# main_bottom.net
KiCad netlist of a schematic drawn in EAGLE
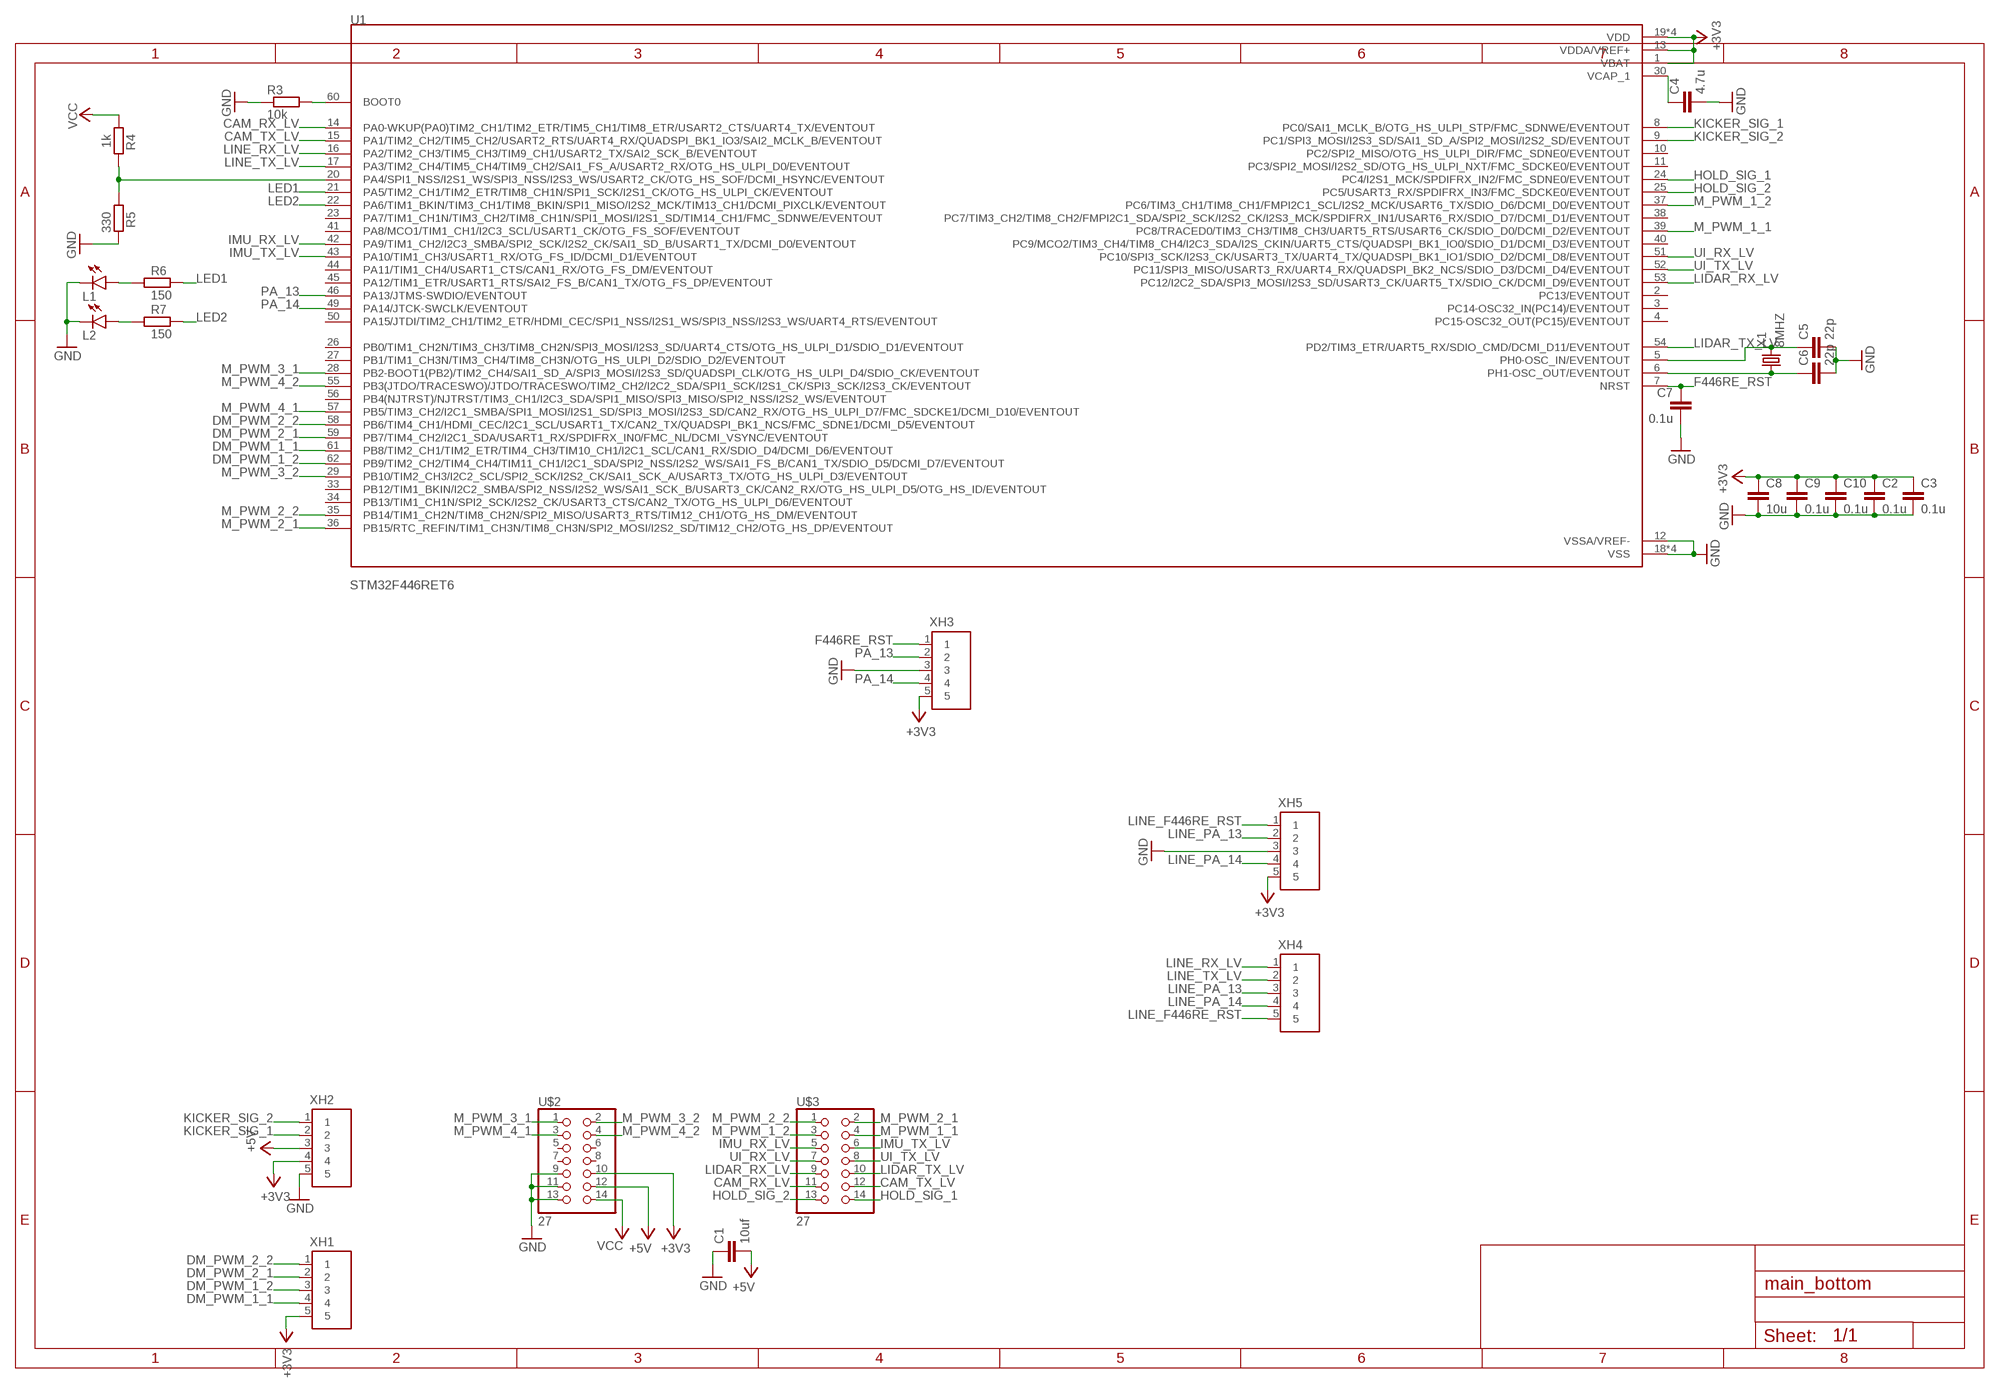
[diagram p0: schematic, sheet 1]

(export (version "E")
  (design (tool "Eeschema 10.0.6"))
  (components
    (comp (ref "C1")
      (value "10uf")
      (footprint "eagle-import:C0805")
      (libsource (lib "eagle-import") (part "C-EUC0805"))
    )
    (comp (ref "C2")
      (value "0.1u")
      (footprint "eagle-import:C0603")
      (libsource (lib "eagle-import") (part "C-EUC0603"))
    )
    (comp (ref "C3")
      (value "0.1u")
      (footprint "eagle-import:C0603")
      (libsource (lib "eagle-import") (part "C-EUC0603"))
    )
    (comp (ref "C4")
      (value "4.7u")
      (footprint "eagle-import:C0603")
      (libsource (lib "eagle-import") (part "C-EUC0603"))
    )
    (comp (ref "C5")
      (value "22p")
      (footprint "eagle-import:C0603")
      (libsource (lib "eagle-import") (part "C-EUC0603"))
    )
    (comp (ref "C6")
      (value "22p")
      (footprint "eagle-import:C0603")
      (libsource (lib "eagle-import") (part "C-EUC0603"))
    )
    (comp (ref "C7")
      (value "0.1u")
      (footprint "eagle-import:C0603")
      (libsource (lib "eagle-import") (part "C-EUC0603"))
    )
    (comp (ref "C8")
      (value "10u")
      (footprint "eagle-import:C0805")
      (libsource (lib "eagle-import") (part "C-EUC0805"))
    )
    (comp (ref "C9")
      (value "0.1u")
      (footprint "eagle-import:C0603")
      (libsource (lib "eagle-import") (part "C-EUC0603"))
    )
    (comp (ref "C10")
      (value "0.1u")
      (footprint "eagle-import:C0603")
      (libsource (lib "eagle-import") (part "C-EUC0603"))
    )
    (comp (ref "L1")
      (value "SML-E12P8WT86")
      (footprint "eagle-import:LED_SML-LXFM0603SIC-TR")
      (libsource (lib "eagle-import") (part "SML-E12P8WT86"))
    )
    (comp (ref "L2")
      (value "SML-E12P8WT86")
      (footprint "eagle-import:LED_SML-LXFM0603SIC-TR")
      (libsource (lib "eagle-import") (part "SML-E12P8WT86"))
    )
    (comp (ref "R3")
      (value "10k")
      (footprint "eagle-import:R0603")
      (libsource (lib "eagle-import") (part "R-EU_R0603"))
    )
    (comp (ref "R4")
      (value "1k")
      (footprint "eagle-import:R0603")
      (libsource (lib "eagle-import") (part "R-EU_R0603"))
    )
    (comp (ref "R5")
      (value "330")
      (footprint "eagle-import:R0603")
      (libsource (lib "eagle-import") (part "R-EU_R0603"))
    )
    (comp (ref "R6")
      (value "150")
      (footprint "eagle-import:R0603")
      (libsource (lib "eagle-import") (part "R-EU_R0603"))
    )
    (comp (ref "R7")
      (value "150")
      (footprint "eagle-import:R0603")
      (libsource (lib "eagle-import") (part "R-EU_R0603"))
    )
    (comp (ref "U$2")
      (value "27")
      (footprint "eagle-import:2_7")
      (libsource (lib "eagle-import") (part "27"))
    )
    (comp (ref "U$3")
      (value "27")
      (footprint "eagle-import:2_7")
      (libsource (lib "eagle-import") (part "27"))
    )
    (comp (ref "U1")
      (value "STM32F446RET6")
      (footprint "eagle-import:QFP50P1200X1200X160-64N")
      (fields (field (name "MF") "STMicroelectronics"))
      (libsource (lib "eagle-import") (part "STM32F446RET6"))
    )
    (comp (ref "X1")
      (value "8MHZ")
      (footprint "eagle-import:16MHZ")
      (libsource (lib "eagle-import") (part "16MHZ"))
    )
    (comp (ref "XH1")
      (value "S5B")
      (footprint "eagle-import:S5B")
      (libsource (lib "eagle-import") (part "S5B"))
    )
    (comp (ref "XH2")
      (value "S5B")
      (footprint "eagle-import:S5B")
      (libsource (lib "eagle-import") (part "S5B"))
    )
    (comp (ref "XH3")
      (value "S5B")
      (footprint "eagle-import:S5B")
      (libsource (lib "eagle-import") (part "S5B"))
    )
    (comp (ref "XH4")
      (value "S5B")
      (footprint "eagle-import:S5B")
      (libsource (lib "eagle-import") (part "S5B"))
    )
    (comp (ref "XH5")
      (value "S5B")
      (footprint "eagle-import:S5B")
      (libsource (lib "eagle-import") (part "S5B"))
    )
  )
  (nets
    (net (code "1") (name "+3V3") (class "Default")
      (node (ref "C10") (pin "1") (pinfunction "1_1") (pintype "passive"))
      (node (ref "C2") (pin "1") (pinfunction "1_1") (pintype "passive"))
      (node (ref "C3") (pin "1") (pinfunction "1_1") (pintype "passive"))
      (node (ref "C8") (pin "1") (pinfunction "1_1") (pintype "passive"))
      (node (ref "C9") (pin "1") (pinfunction "1_1") (pintype "passive"))
      (node (ref "U$2") (pin "10") (pinfunction "10_10") (pintype "passive"))
      (node (ref "U1") (pin "1") (pinfunction "VBAT_1") (pintype "power_in"))
      (node (ref "U1") (pin "13") (pinfunction "VDDA/VREF+_13") (pintype "power_in"))
      (node (ref "U1") (pin "19") (pinfunction "VDD_19") (pintype "power_in"))
      (node (ref "U1") (pin "32") (pinfunction "VDD_32") (pintype "power_in"))
      (node (ref "U1") (pin "48") (pinfunction "VDD_48") (pintype "power_in"))
      (node (ref "U1") (pin "64") (pinfunction "VDD_64") (pintype "power_in"))
      (node (ref "XH1") (pin "5") (pinfunction "5_5") (pintype "bidirectional"))
      (node (ref "XH2") (pin "4") (pinfunction "4_4") (pintype "bidirectional"))
      (node (ref "XH3") (pin "5") (pinfunction "5_5") (pintype "bidirectional"))
      (node (ref "XH5") (pin "5") (pinfunction "5_5") (pintype "bidirectional"))
    )
    (net (code "2") (name "+5V") (class "Default")
      (node (ref "C1") (pin "2") (pinfunction "2_2") (pintype "passive"))
      (node (ref "U$2") (pin "12") (pinfunction "12_12") (pintype "passive"))
      (node (ref "XH2") (pin "3") (pinfunction "3_3") (pintype "bidirectional"))
    )
    (net (code "3") (name "/CAM_RX_LV") (class "Default")
      (node (ref "U$3") (pin "11") (pinfunction "11_11") (pintype "passive"))
      (node (ref "U1") (pin "14") (pinfunction "PA0-WKUP(PA0)TIM2_CH1/TIM2_ETR/TIM5_CH1/TIM8_ETR/USART2_CTS/UART4_TX/EVENTOUT_14") (pintype "bidirectional"))
    )
    (net (code "4") (name "/CAM_TX_LV") (class "Default")
      (node (ref "U$3") (pin "12") (pinfunction "12_12") (pintype "passive"))
      (node (ref "U1") (pin "15") (pinfunction "PA1/TIM2_CH2/TIM5_CH2/USART2_RTS/UART4_RX/QUADSPI_BK1_IO3/SAI2_MCLK_B/EVENTOUT_15") (pintype "bidirectional"))
    )
    (net (code "5") (name "/DM_PWM_1_1") (class "Default")
      (node (ref "U1") (pin "61") (pinfunction "PB8/TIM2_CH1/TIM2_ETR/TIM4_CH3/TIM10_CH1/I2C1_SCL/CAN1_RX/SDIO_D4/DCMI_D6/EVENTOUT_61") (pintype "bidirectional"))
      (node (ref "XH1") (pin "4") (pinfunction "4_4") (pintype "bidirectional"))
    )
    (net (code "6") (name "/DM_PWM_1_2") (class "Default")
      (node (ref "U1") (pin "62") (pinfunction "PB9/TIM2_CH2/TIM4_CH4/TIM11_CH1/I2C1_SDA/SPI2_NSS/I2S2_WS/SAI1_FS_B/CAN1_TX/SDIO_D5/DCMI_D7/EVENTOUT_62") (pintype "bidirectional"))
      (node (ref "XH1") (pin "3") (pinfunction "3_3") (pintype "bidirectional"))
    )
    (net (code "7") (name "/DM_PWM_2_1") (class "Default")
      (node (ref "U1") (pin "59") (pinfunction "PB7/TIM4_CH2/I2C1_SDA/USART1_RX/SPDIFRX_IN0/FMC_NL/DCMI_VSYNC/EVENTOUT_59") (pintype "bidirectional"))
      (node (ref "XH1") (pin "2") (pinfunction "2_2") (pintype "bidirectional"))
    )
    (net (code "8") (name "/DM_PWM_2_2") (class "Default")
      (node (ref "U1") (pin "58") (pinfunction "PB6/TIM4_CH1/HDMI_CEC/I2C1_SCL/USART1_TX/CAN2_TX/QUADSPI_BK1_NCS/FMC_SDNE1/DCMI_D5/EVENTOUT_58") (pintype "bidirectional"))
      (node (ref "XH1") (pin "1") (pinfunction "1_1") (pintype "bidirectional"))
    )
    (net (code "9") (name "/F446RE_RST") (class "Default")
      (node (ref "C7") (pin "1") (pinfunction "1_1") (pintype "passive"))
      (node (ref "U1") (pin "7") (pinfunction "NRST_7") (pintype "bidirectional"))
      (node (ref "XH3") (pin "1") (pinfunction "1_1") (pintype "bidirectional"))
    )
    (net (code "10") (name "/HOLD_SIG_1") (class "Default")
      (node (ref "U$3") (pin "14") (pinfunction "14_14") (pintype "passive"))
      (node (ref "U1") (pin "24") (pinfunction "PC4/I2S1_MCK/SPDIFRX_IN2/FMC_SDNE0/EVENTOUT_24") (pintype "bidirectional"))
    )
    (net (code "11") (name "/HOLD_SIG_2") (class "Default")
      (node (ref "U$3") (pin "13") (pinfunction "13_13") (pintype "passive"))
      (node (ref "U1") (pin "25") (pinfunction "PC5/USART3_RX/SPDIFRX_IN3/FMC_SDCKE0/EVENTOUT_25") (pintype "bidirectional"))
    )
    (net (code "12") (name "/IMU_RX_LV") (class "Default")
      (node (ref "U$3") (pin "5") (pinfunction "5_5") (pintype "passive"))
      (node (ref "U1") (pin "42") (pinfunction "PA9/TIM1_CH2/I2C3_SMBA/SPI2_SCK/I2S2_CK/SAI1_SD_B/USART1_TX/DCMI_D0/EVENTOUT_42") (pintype "bidirectional"))
    )
    (net (code "13") (name "/IMU_TX_LV") (class "Default")
      (node (ref "U$3") (pin "6") (pinfunction "6_6") (pintype "passive"))
      (node (ref "U1") (pin "43") (pinfunction "PA10/TIM1_CH3/USART1_RX/OTG_FS_ID/DCMI_D1/EVENTOUT_43") (pintype "bidirectional"))
    )
    (net (code "14") (name "/KICKER_SIG_1") (class "Default")
      (node (ref "U1") (pin "8") (pinfunction "PC0/SAI1_MCLK_B/OTG_HS_ULPI_STP/FMC_SDNWE/EVENTOUT_8") (pintype "bidirectional"))
      (node (ref "XH2") (pin "2") (pinfunction "2_2") (pintype "bidirectional"))
    )
    (net (code "15") (name "/KICKER_SIG_2") (class "Default")
      (node (ref "U1") (pin "9") (pinfunction "PC1/SPI3_MOSI/I2S3_SD/SAI1_SD_A/SPI2_MOSI/I2S2_SD/EVENTOUT_9") (pintype "bidirectional"))
      (node (ref "XH2") (pin "1") (pinfunction "1_1") (pintype "bidirectional"))
    )
    (net (code "16") (name "/LED1") (class "Default")
      (node (ref "R6") (pin "2") (pinfunction "2_2") (pintype "passive"))
      (node (ref "U1") (pin "21") (pinfunction "PA5/TIM2_CH1/TIM2_ETR/TIM8_CH1N/SPI1_SCK/I2S1_CK/OTG_HS_ULPI_CK/EVENTOUT_21") (pintype "bidirectional"))
    )
    (net (code "17") (name "/LED2") (class "Default")
      (node (ref "R7") (pin "2") (pinfunction "2_2") (pintype "passive"))
      (node (ref "U1") (pin "22") (pinfunction "PA6/TIM1_BKIN/TIM3_CH1/TIM8_BKIN/SPI1_MISO/I2S2_MCK/TIM13_CH1/DCMI_PIXCLK/EVENTOUT_22") (pintype "bidirectional"))
    )
    (net (code "18") (name "/LIDAR_RX_LV") (class "Default")
      (node (ref "U$3") (pin "9") (pinfunction "9_9") (pintype "passive"))
      (node (ref "U1") (pin "53") (pinfunction "PC12/I2C2_SDA/SPI3_MOSI/I2S3_SD/USART3_CK/UART5_TX/SDIO_CK/DCMI_D9/EVENTOUT_53") (pintype "bidirectional"))
    )
    (net (code "19") (name "/LIDAR_TX_LV") (class "Default")
      (node (ref "U$3") (pin "10") (pinfunction "10_10") (pintype "passive"))
      (node (ref "U1") (pin "54") (pinfunction "PD2/TIM3_ETR/UART5_RX/SDIO_CMD/DCMI_D11/EVENTOUT_54") (pintype "bidirectional"))
    )
    (net (code "20") (name "/LINE_F446RE_RST") (class "Default")
      (node (ref "XH4") (pin "5") (pinfunction "5_5") (pintype "bidirectional"))
      (node (ref "XH5") (pin "1") (pinfunction "1_1") (pintype "bidirectional"))
    )
    (net (code "21") (name "/LINE_PA_13") (class "Default")
      (node (ref "XH4") (pin "3") (pinfunction "3_3") (pintype "bidirectional"))
      (node (ref "XH5") (pin "2") (pinfunction "2_2") (pintype "bidirectional"))
    )
    (net (code "22") (name "/LINE_PA_14") (class "Default")
      (node (ref "XH4") (pin "4") (pinfunction "4_4") (pintype "bidirectional"))
      (node (ref "XH5") (pin "4") (pinfunction "4_4") (pintype "bidirectional"))
    )
    (net (code "23") (name "/LINE_RX_LV") (class "Default")
      (node (ref "U1") (pin "16") (pinfunction "PA2/TIM2_CH3/TIM5_CH3/TIM9_CH1/USART2_TX/SAI2_SCK_B/EVENTOUT_16") (pintype "bidirectional"))
      (node (ref "XH4") (pin "1") (pinfunction "1_1") (pintype "bidirectional"))
    )
    (net (code "24") (name "/LINE_TX_LV") (class "Default")
      (node (ref "U1") (pin "17") (pinfunction "PA3/TIM2_CH4/TIM5_CH4/TIM9_CH2/SAI1_FS_A/USART2_RX/OTG_HS_ULPI_D0/EVENTOUT_17") (pintype "bidirectional"))
      (node (ref "XH4") (pin "2") (pinfunction "2_2") (pintype "bidirectional"))
    )
    (net (code "25") (name "/M_PWM_1_1") (class "Default")
      (node (ref "U$3") (pin "4") (pinfunction "4_4") (pintype "passive"))
      (node (ref "U1") (pin "39") (pinfunction "PC8/TRACED0/TIM3_CH3/TIM8_CH3/UART5_RTS/USART6_CK/SDIO_D0/DCMI_D2/EVENTOUT_39") (pintype "bidirectional"))
    )
    (net (code "26") (name "/M_PWM_1_2") (class "Default")
      (node (ref "U$3") (pin "3") (pinfunction "3_3") (pintype "passive"))
      (node (ref "U1") (pin "37") (pinfunction "PC6/TIM3_CH1/TIM8_CH1/FMPI2C1_SCL/I2S2_MCK/USART6_TX/SDIO_D6/DCMI_D0/EVENTOUT_37") (pintype "bidirectional"))
    )
    (net (code "27") (name "/M_PWM_2_1") (class "Default")
      (node (ref "U$3") (pin "2") (pinfunction "2_2") (pintype "passive"))
      (node (ref "U1") (pin "36") (pinfunction "PB15/RTC_REFIN/TIM1_CH3N/TIM8_CH3N/SPI2_MOSI/I2S2_SD/TIM12_CH2/OTG_HS_DP/EVENTOUT_36") (pintype "bidirectional"))
    )
    (net (code "28") (name "/M_PWM_2_2") (class "Default")
      (node (ref "U$3") (pin "1") (pinfunction "1_1") (pintype "passive"))
      (node (ref "U1") (pin "35") (pinfunction "PB14/TIM1_CH2N/TIM8_CH2N/SPI2_MISO/USART3_RTS/TIM12_CH1/OTG_HS_DM/EVENTOUT_35") (pintype "bidirectional"))
    )
    (net (code "29") (name "/M_PWM_3_1") (class "Default")
      (node (ref "U$2") (pin "1") (pinfunction "1_1") (pintype "passive"))
      (node (ref "U1") (pin "28") (pinfunction "PB2-BOOT1(PB2)/TIM2_CH4/SAI1_SD_A/SPI3_MOSI/I2S3_SD/QUADSPI_CLK/OTG_HS_ULPI_D4/SDIO_CK/EVENTOUT_28") (pintype "bidirectional"))
    )
    (net (code "30") (name "/M_PWM_3_2") (class "Default")
      (node (ref "U$2") (pin "2") (pinfunction "2_2") (pintype "passive"))
      (node (ref "U1") (pin "29") (pinfunction "PB10/TIM2_CH3/I2C2_SCL/SPI2_SCK/I2S2_CK/SAI1_SCK_A/USART3_TX/OTG_HS_ULPI_D3/EVENTOUT_29") (pintype "bidirectional"))
    )
    (net (code "31") (name "/M_PWM_4_1") (class "Default")
      (node (ref "U$2") (pin "3") (pinfunction "3_3") (pintype "passive"))
      (node (ref "U1") (pin "57") (pinfunction "PB5/TIM3_CH2/I2C1_SMBA/SPI1_MOSI/I2S1_SD/SPI3_MOSI/I2S3_SD/CAN2_RX/OTG_HS_ULPI_D7/FMC_SDCKE1/DCMI_D10/EVENTOUT_57") (pintype "bidirectional"))
    )
    (net (code "32") (name "/M_PWM_4_2") (class "Default")
      (node (ref "U$2") (pin "4") (pinfunction "4_4") (pintype "passive"))
      (node (ref "U1") (pin "55") (pinfunction "PB3(JTDO/TRACESWO)/JTDO/TRACESWO/TIM2_CH2/I2C2_SDA/SPI1_SCK/I2S1_CK/SPI3_SCK/I2S3_CK/EVENTOUT_55") (pintype "bidirectional"))
    )
    (net (code "33") (name "/PA_13") (class "Default")
      (node (ref "U1") (pin "46") (pinfunction "PA13/JTMS-SWDIO/EVENTOUT_46") (pintype "bidirectional"))
      (node (ref "XH3") (pin "2") (pinfunction "2_2") (pintype "bidirectional"))
    )
    (net (code "34") (name "/PA_14") (class "Default")
      (node (ref "U1") (pin "49") (pinfunction "PA14/JTCK-SWCLK/EVENTOUT_49") (pintype "bidirectional"))
      (node (ref "XH3") (pin "4") (pinfunction "4_4") (pintype "bidirectional"))
    )
    (net (code "35") (name "/UI_RX_LV") (class "Default")
      (node (ref "U$3") (pin "7") (pinfunction "7_7") (pintype "passive"))
      (node (ref "U1") (pin "51") (pinfunction "PC10/SPI3_SCK/I2S3_CK/USART3_TX/UART4_TX/QUADSPI_BK1_IO1/SDIO_D2/DCMI_D8/EVENTOUT_51") (pintype "bidirectional"))
    )
    (net (code "36") (name "/UI_TX_LV") (class "Default")
      (node (ref "U$3") (pin "8") (pinfunction "8_8") (pintype "passive"))
      (node (ref "U1") (pin "52") (pinfunction "PC11/SPI3_MISO/USART3_RX/UART4_RX/QUADSPI_BK2_NCS/SDIO_D3/DCMI_D4/EVENTOUT_52") (pintype "bidirectional"))
    )
    (net (code "37") (name "GND") (class "Default")
      (node (ref "C1") (pin "1") (pinfunction "1_1") (pintype "passive"))
      (node (ref "C10") (pin "2") (pinfunction "2_2") (pintype "passive"))
      (node (ref "C2") (pin "2") (pinfunction "2_2") (pintype "passive"))
      (node (ref "C3") (pin "2") (pinfunction "2_2") (pintype "passive"))
      (node (ref "C4") (pin "2") (pinfunction "2_2") (pintype "passive"))
      (node (ref "C5") (pin "2") (pinfunction "2_2") (pintype "passive"))
      (node (ref "C6") (pin "2") (pinfunction "2_2") (pintype "passive"))
      (node (ref "C7") (pin "2") (pinfunction "2_2") (pintype "passive"))
      (node (ref "C8") (pin "2") (pinfunction "2_2") (pintype "passive"))
      (node (ref "C9") (pin "2") (pinfunction "2_2") (pintype "passive"))
      (node (ref "L1") (pin "C") (pinfunction "C_C") (pintype "passive"))
      (node (ref "L2") (pin "C") (pinfunction "C_C") (pintype "passive"))
      (node (ref "R3") (pin "1") (pinfunction "1_1") (pintype "passive"))
      (node (ref "R5") (pin "2") (pinfunction "2_2") (pintype "passive"))
      (node (ref "U$2") (pin "11") (pinfunction "11_11") (pintype "passive"))
      (node (ref "U$2") (pin "13") (pinfunction "13_13") (pintype "passive"))
      (node (ref "U$2") (pin "9") (pinfunction "9_9") (pintype "passive"))
      (node (ref "U1") (pin "12") (pinfunction "VSSA/VREF-_12") (pintype "power_in"))
      (node (ref "U1") (pin "18") (pinfunction "VSS_18") (pintype "power_in"))
      (node (ref "U1") (pin "31") (pinfunction "VSS_31") (pintype "power_in"))
      (node (ref "U1") (pin "47") (pinfunction "VSS_47") (pintype "power_in"))
      (node (ref "U1") (pin "63") (pinfunction "VSS_63") (pintype "power_in"))
      (node (ref "XH2") (pin "5") (pinfunction "5_5") (pintype "bidirectional"))
      (node (ref "XH3") (pin "3") (pinfunction "3_3") (pintype "bidirectional"))
      (node (ref "XH5") (pin "3") (pinfunction "3_3") (pintype "bidirectional"))
    )
    (net (code "38") (name "Net-(L1-PadA)") (class "Default")
      (node (ref "L1") (pin "A") (pinfunction "A_A") (pintype "passive"))
      (node (ref "R6") (pin "1") (pinfunction "1_1") (pintype "passive"))
    )
    (net (code "39") (name "Net-(L2-PadA)") (class "Default")
      (node (ref "L2") (pin "A") (pinfunction "A_A") (pintype "passive"))
      (node (ref "R7") (pin "1") (pinfunction "1_1") (pintype "passive"))
    )
    (net (code "40") (name "Net-(U1-BOOT0)") (class "Default")
      (node (ref "R3") (pin "2") (pinfunction "2_2") (pintype "passive"))
      (node (ref "U1") (pin "60") (pinfunction "BOOT0_60") (pintype "input"))
    )
    (net (code "41") (name "Net-(U1-PA4{slash}SPI1_NSS{slash}I2S1_WS{slash}SPI3_NSS{slash}I2S3_WS{slash}USART2_CK{slash}OTG_HS_SOF{slash}DCMI_HSYNC{slash}EVENTOUT)") (class "Default")
      (node (ref "R4") (pin "2") (pinfunction "2_2") (pintype "passive"))
      (node (ref "R5") (pin "1") (pinfunction "1_1") (pintype "passive"))
      (node (ref "U1") (pin "20") (pinfunction "PA4/SPI1_NSS/I2S1_WS/SPI3_NSS/I2S3_WS/USART2_CK/OTG_HS_SOF/DCMI_HSYNC/EVENTOUT_20") (pintype "bidirectional"))
    )
    (net (code "42") (name "Net-(U1-PH0-OSC_IN{slash}EVENTOUT)") (class "Default")
      (node (ref "C5") (pin "1") (pinfunction "1_1") (pintype "passive"))
      (node (ref "U1") (pin "5") (pinfunction "PH0-OSC_IN/EVENTOUT_5") (pintype "bidirectional"))
      (node (ref "X1") (pin "P$2") (pinfunction "2_P$2") (pintype "passive"))
    )
    (net (code "43") (name "Net-(U1-PH1-OSC_OUT{slash}EVENTOUT)") (class "Default")
      (node (ref "C6") (pin "1") (pinfunction "1_1") (pintype "passive"))
      (node (ref "U1") (pin "6") (pinfunction "PH1-OSC_OUT/EVENTOUT_6") (pintype "bidirectional"))
      (node (ref "X1") (pin "P$1") (pinfunction "1_P$1") (pintype "passive"))
    )
    (net (code "44") (name "Net-(U1-VCAP_1)") (class "Default")
      (node (ref "C4") (pin "1") (pinfunction "1_1") (pintype "passive"))
      (node (ref "U1") (pin "30") (pinfunction "VCAP_1_30") (pintype "power_in"))
    )
    (net (code "45") (name "VCC") (class "Default")
      (node (ref "R4") (pin "1") (pinfunction "1_1") (pintype "passive"))
      (node (ref "U$2") (pin "14") (pinfunction "14_14") (pintype "passive"))
    )
    (net (code "46") (name "unconnected-(U$2-Pad5)") (class "Default")
      (node (ref "U$2") (pin "5") (pinfunction "5_5") (pintype "passive"))
    )
    (net (code "47") (name "unconnected-(U$2-Pad6)") (class "Default")
      (node (ref "U$2") (pin "6") (pinfunction "6_6") (pintype "passive"))
    )
    (net (code "48") (name "unconnected-(U$2-Pad7)") (class "Default")
      (node (ref "U$2") (pin "7") (pinfunction "7_7") (pintype "passive"))
    )
    (net (code "49") (name "unconnected-(U$2-Pad8)") (class "Default")
      (node (ref "U$2") (pin "8") (pinfunction "8_8") (pintype "passive"))
    )
    (net (code "50") (name "unconnected-(U1-PA7{slash}TIM1_CH1N{slash}TIM3_CH2{slash}TIM8_CH1N{slash}SPI1_MOSI{slash}I2S1_SD{slash}TIM14_CH1{slash}FMC_SDNWE{slash}EVENTOUT-Pad23)") (class "Default")
      (node (ref "U1") (pin "23") (pinfunction "PA7/TIM1_CH1N/TIM3_CH2/TIM8_CH1N/SPI1_MOSI/I2S1_SD/TIM14_CH1/FMC_SDNWE/EVENTOUT_23") (pintype "bidirectional"))
    )
    (net (code "51") (name "unconnected-(U1-PA8{slash}MCO1{slash}TIM1_CH1{slash}I2C3_SCL{slash}USART1_CK{slash}OTG_FS_SOF{slash}EVENTOUT-Pad41)") (class "Default")
      (node (ref "U1") (pin "41") (pinfunction "PA8/MCO1/TIM1_CH1/I2C3_SCL/USART1_CK/OTG_FS_SOF/EVENTOUT_41") (pintype "bidirectional"))
    )
    (net (code "52") (name "unconnected-(U1-PA11{slash}TIM1_CH4{slash}USART1_CTS{slash}CAN1_RX{slash}OTG_FS_DM{slash}EVENTOUT-Pad44)") (class "Default")
      (node (ref "U1") (pin "44") (pinfunction "PA11/TIM1_CH4/USART1_CTS/CAN1_RX/OTG_FS_DM/EVENTOUT_44") (pintype "bidirectional"))
    )
    (net (code "53") (name "unconnected-(U1-PA12{slash}TIM1_ETR{slash}USART1_RTS{slash}SAI2_FS_B{slash}CAN1_TX{slash}OTG_FS_DP{slash}EVENTOUT-Pad45)") (class "Default")
      (node (ref "U1") (pin "45") (pinfunction "PA12/TIM1_ETR/USART1_RTS/SAI2_FS_B/CAN1_TX/OTG_FS_DP/EVENTOUT_45") (pintype "bidirectional"))
    )
    (net (code "54") (name "unconnected-(U1-PA15{slash}JTDI{slash}TIM2_CH1{slash}TIM2_ETR{slash}HDMI_CEC{slash}SPI1_NSS{slash}I2S1_WS{slash}SPI3_NSS{slash}I2S3_WS{slash}UART4_RTS{slash}EVENTOUT-Pad50)") (class "Default")
      (node (ref "U1") (pin "50") (pinfunction "PA15/JTDI/TIM2_CH1/TIM2_ETR/HDMI_CEC/SPI1_NSS/I2S1_WS/SPI3_NSS/I2S3_WS/UART4_RTS/EVENTOUT_50") (pintype "bidirectional"))
    )
    (net (code "55") (name "unconnected-(U1-PB0{slash}TIM1_CH2N{slash}TIM3_CH3{slash}TIM8_CH2N{slash}SPI3_MOSI{slash}I2S3_SD{slash}UART4_CTS{slash}OTG_HS_ULPI_D1{slash}SDIO_D1{slash}EVENTOUT-Pad26)") (class "Default")
      (node (ref "U1") (pin "26") (pinfunction "PB0/TIM1_CH2N/TIM3_CH3/TIM8_CH2N/SPI3_MOSI/I2S3_SD/UART4_CTS/OTG_HS_ULPI_D1/SDIO_D1/EVENTOUT_26") (pintype "bidirectional"))
    )
    (net (code "56") (name "unconnected-(U1-PB1{slash}TIM1_CH3N{slash}TIM3_CH4{slash}TIM8_CH3N{slash}OTG_HS_ULPI_D2{slash}SDIO_D2{slash}EVENTOUT-Pad27)") (class "Default")
      (node (ref "U1") (pin "27") (pinfunction "PB1/TIM1_CH3N/TIM3_CH4/TIM8_CH3N/OTG_HS_ULPI_D2/SDIO_D2/EVENTOUT_27") (pintype "bidirectional"))
    )
    (net (code "57") (name "unconnected-(U1-PB4(NJTRST){slash}NJTRST{slash}TIM3_CH1{slash}I2C3_SDA{slash}SPI1_MISO{slash}SPI3_MISO{slash}SPI2_NSS{slash}I2S2_WS{slash}EVENTOUT-Pad56)") (class "Default")
      (node (ref "U1") (pin "56") (pinfunction "PB4(NJTRST)/NJTRST/TIM3_CH1/I2C3_SDA/SPI1_MISO/SPI3_MISO/SPI2_NSS/I2S2_WS/EVENTOUT_56") (pintype "bidirectional"))
    )
    (net (code "58") (name "unconnected-(U1-PB12{slash}TIM1_BKIN{slash}I2C2_SMBA{slash}SPI2_NSS{slash}I2S2_WS{slash}SAI1_SCK_B{slash}USART3_CK{slash}CAN2_RX{slash}OTG_HS_ULPI_D5{slash}OTG_HS_ID{slash}EVENTOUT-Pad33)") (class "Default")
      (node (ref "U1") (pin "33") (pinfunction "PB12/TIM1_BKIN/I2C2_SMBA/SPI2_NSS/I2S2_WS/SAI1_SCK_B/USART3_CK/CAN2_RX/OTG_HS_ULPI_D5/OTG_HS_ID/EVENTOUT_33") (pintype "bidirectional"))
    )
    (net (code "59") (name "unconnected-(U1-PB13{slash}TIM1_CH1N{slash}SPI2_SCK{slash}I2S2_CK{slash}USART3_CTS{slash}CAN2_TX{slash}OTG_HS_ULPI_D6{slash}EVENTOUT-Pad34)") (class "Default")
      (node (ref "U1") (pin "34") (pinfunction "PB13/TIM1_CH1N/SPI2_SCK/I2S2_CK/USART3_CTS/CAN2_TX/OTG_HS_ULPI_D6/EVENTOUT_34") (pintype "bidirectional"))
    )
    (net (code "60") (name "unconnected-(U1-PC2{slash}SPI2_MISO{slash}OTG_HS_ULPI_DIR{slash}FMC_SDNE0{slash}EVENTOUT-Pad10)") (class "Default")
      (node (ref "U1") (pin "10") (pinfunction "PC2/SPI2_MISO/OTG_HS_ULPI_DIR/FMC_SDNE0/EVENTOUT_10") (pintype "bidirectional"))
    )
    (net (code "61") (name "unconnected-(U1-PC3{slash}SPI2_MOSI{slash}I2S2_SD{slash}OTG_HS_ULPI_NXT{slash}FMC_SDCKE0{slash}EVENTOUT-Pad11)") (class "Default")
      (node (ref "U1") (pin "11") (pinfunction "PC3/SPI2_MOSI/I2S2_SD/OTG_HS_ULPI_NXT/FMC_SDCKE0/EVENTOUT_11") (pintype "bidirectional"))
    )
    (net (code "62") (name "unconnected-(U1-PC7{slash}TIM3_CH2{slash}TIM8_CH2{slash}FMPI2C1_SDA{slash}SPI2_SCK{slash}I2S2_CK{slash}I2S3_MCK{slash}SPDIFRX_IN1{slash}USART6_RX{slash}SDIO_D7{slash}DCMI_D1{slash}EVENTOUT-Pad38)") (class "Default")
      (node (ref "U1") (pin "38") (pinfunction "PC7/TIM3_CH2/TIM8_CH2/FMPI2C1_SDA/SPI2_SCK/I2S2_CK/I2S3_MCK/SPDIFRX_IN1/USART6_RX/SDIO_D7/DCMI_D1/EVENTOUT_38") (pintype "bidirectional"))
    )
    (net (code "63") (name "unconnected-(U1-PC9{slash}MCO2{slash}TIM3_CH4{slash}TIM8_CH4{slash}I2C3_SDA{slash}I2S_CKIN{slash}UART5_CTS{slash}QUADSPI_BK1_IO0{slash}SDIO_D1{slash}DCMI_D3{slash}EVENTOUT-Pad40)") (class "Default")
      (node (ref "U1") (pin "40") (pinfunction "PC9/MCO2/TIM3_CH4/TIM8_CH4/I2C3_SDA/I2S_CKIN/UART5_CTS/QUADSPI_BK1_IO0/SDIO_D1/DCMI_D3/EVENTOUT_40") (pintype "bidirectional"))
    )
    (net (code "64") (name "unconnected-(U1-PC13{slash}EVENTOUT-Pad2)") (class "Default")
      (node (ref "U1") (pin "2") (pinfunction "PC13/EVENTOUT_2") (pintype "bidirectional"))
    )
    (net (code "65") (name "unconnected-(U1-PC14-OSC32_IN(PC14){slash}EVENTOUT-Pad3)") (class "Default")
      (node (ref "U1") (pin "3") (pinfunction "PC14-OSC32_IN(PC14)/EVENTOUT_3") (pintype "bidirectional"))
    )
    (net (code "66") (name "unconnected-(U1-PC15-OSC32_OUT(PC15){slash}EVENTOUT-Pad4)") (class "Default")
      (node (ref "U1") (pin "4") (pinfunction "PC15-OSC32_OUT(PC15)/EVENTOUT_4") (pintype "bidirectional"))
    )
  )
)
